# OpenRing_MCU.net
KiCad netlist of a schematic drawn in Altium Designer
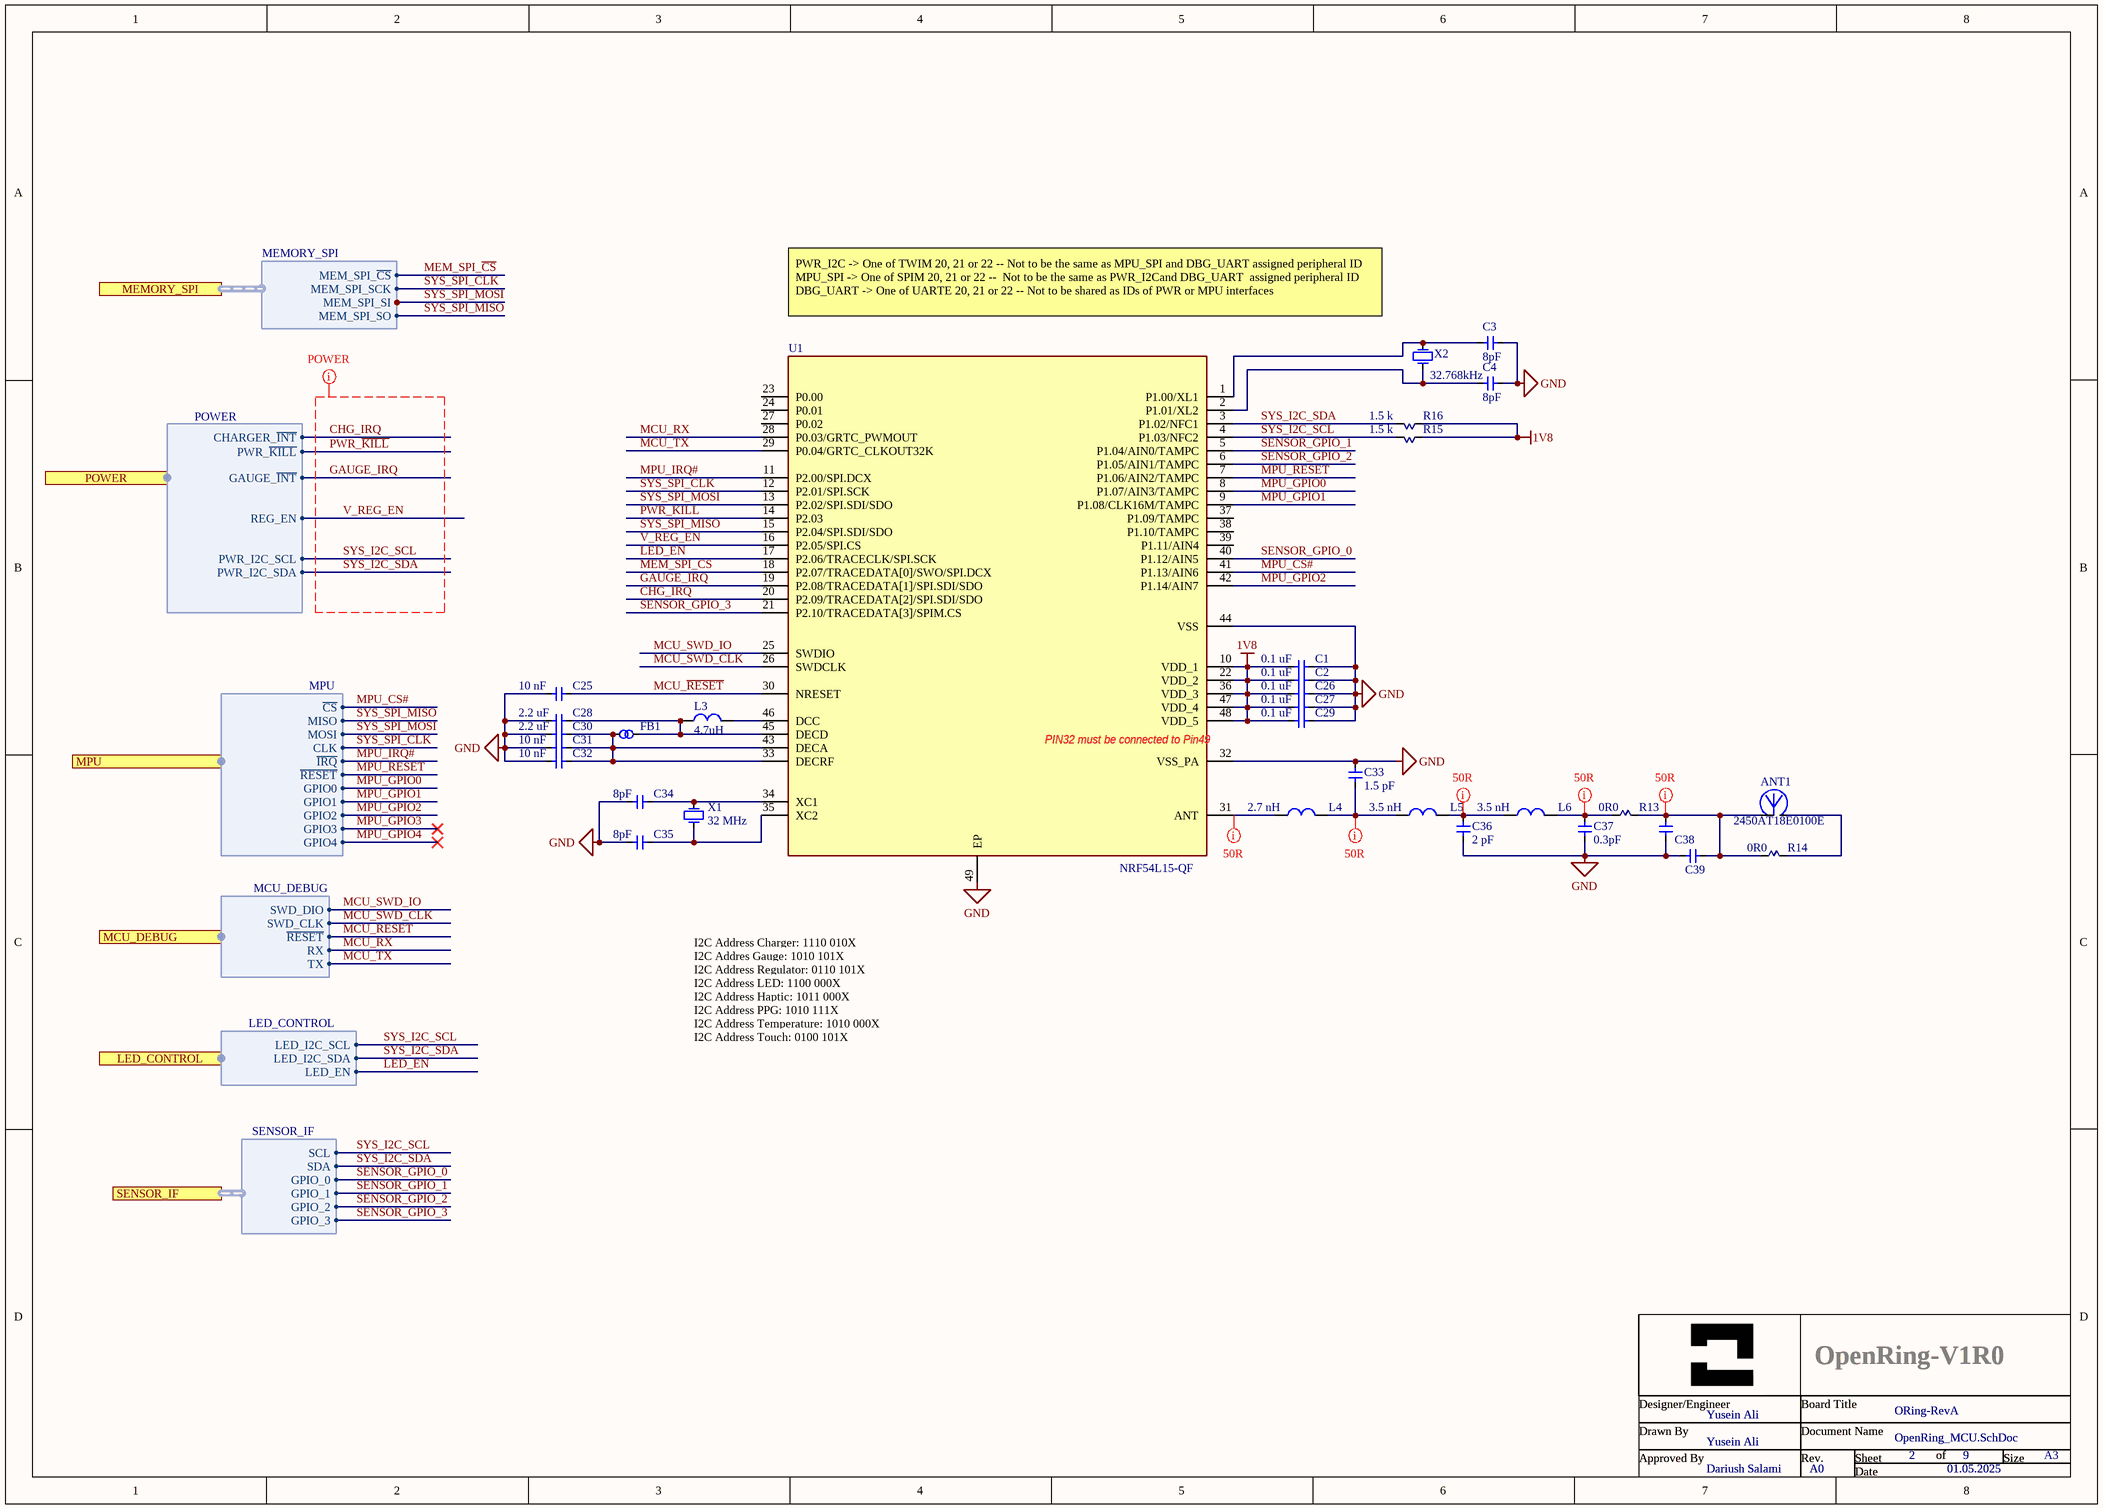
[diagram p0: OpenRing_MCU.SchDoc]

(export (version "E")
  (design (tool "Eeschema 10.0.6"))
  (components
    (comp (ref "ANT1")
      (value "2450AT18E0100E")
      (footprint "ANTC3216X130N")
      (description "7 Inch Reel / Mini 2.45Ghz Chip Antenna")
      (fields (field (name "MANUFACTURER") "Johanson") (field (name "CHECKED") "TRUE"))
      (libsource (lib "RFComponents") (part "2450AT18E0100E"))
    )
    (comp (ref "C1")
      (value "0.1 uF")
      (footprint "CAPC1005X05N")
      (description "CAP CER 0.1UF 16V X5R 0402")
      (fields
        (field (name "MANUFACTURER") "Murata Electronics")
        (field (name "MANUFACTURER PART NUMBER") "GRM155R61C104KA88D")
      )
      (libsource (lib "OpenRingComponents") (part "GRM155R61C104KA88D"))
    )
    (comp (ref "C2")
      (value "0.1 uF")
      (footprint "CAPC1005X05N")
      (description "CAP CER 0.1UF 16V X5R 0402")
      (fields
        (field (name "MANUFACTURER") "Murata Electronics")
        (field (name "MANUFACTURER PART NUMBER") "GRM155R61C104KA88D")
      )
      (libsource (lib "OpenRingComponents") (part "GRM155R61C104KA88D"))
    )
    (comp (ref "C3")
      (value "8pF")
      (footprint "CAPC1005X05N")
      (description "Multilayer Ceramic Capacitors MLCC - SMD/SMT 0402 8.0pF 50volts C0G +/-0.05pF")
      (fields
        (field (name "MANUFACTURER") "Murata")
        (field (name "MANUFACTURER PART NUMBER") "GRM1555C1H8R0BA01D")
      )
      (libsource (lib "OpenRingComponents") (part "GRM1555C1H8R0BA01D"))
    )
    (comp (ref "C4")
      (value "8pF")
      (footprint "CAPC1005X05N")
      (description "Multilayer Ceramic Capacitors MLCC - SMD/SMT 0402 8.0pF 50volts C0G +/-0.05pF")
      (fields
        (field (name "MANUFACTURER") "Murata")
        (field (name "MANUFACTURER PART NUMBER") "GRM1555C1H8R0BA01D")
      )
      (libsource (lib "OpenRingComponents") (part "GRM1555C1H8R0BA01D"))
    )
    (comp (ref "C25")
      (value "10 nF")
      (footprint "CAPC1005X05N")
      (description "CAP CER 10000PF 50V X7R 0402")
      (fields
        (field (name "MANUFACTURER") "Murata Electronics North America")
        (field (name "MANUFACTURER PART NUMBER") "GRM155R71H103KA88D")
      )
      (libsource (lib "OpenRingComponents") (part "GRM155R71H103KA88D"))
    )
    (comp (ref "C26")
      (value "0.1 uF")
      (footprint "CAPC1005X05N")
      (description "CAP CER 0.1UF 16V X5R 0402")
      (fields
        (field (name "MANUFACTURER") "Murata Electronics")
        (field (name "MANUFACTURER PART NUMBER") "GRM155R61C104KA88D")
      )
      (libsource (lib "OpenRingComponents") (part "GRM155R61C104KA88D"))
    )
    (comp (ref "C27")
      (value "0.1 uF")
      (footprint "CAPC1005X05N")
      (description "CAP CER 0.1UF 16V X5R 0402")
      (fields
        (field (name "MANUFACTURER") "Murata Electronics")
        (field (name "MANUFACTURER PART NUMBER") "GRM155R61C104KA88D")
      )
      (libsource (lib "OpenRingComponents") (part "GRM155R61C104KA88D"))
    )
    (comp (ref "C28")
      (value "2.2 uF")
      (footprint "CAPC1005X05N")
      (description "CAP CER 2.2UF 10V X5R 0402")
      (fields
        (field (name "MANUFACTURER") "Murata Electronics North America")
        (field (name "MANUFACTURER PART NUMBER") "GRM155R61A225KE95D")
      )
      (libsource (lib "OpenRingComponents") (part "GRM155R61A225KE95D"))
    )
    (comp (ref "C29")
      (value "0.1 uF")
      (footprint "CAPC1005X05N")
      (description "CAP CER 0.1UF 16V X5R 0402")
      (fields
        (field (name "MANUFACTURER") "Murata Electronics")
        (field (name "MANUFACTURER PART NUMBER") "GRM155R61C104KA88D")
      )
      (libsource (lib "OpenRingComponents") (part "GRM155R61C104KA88D"))
    )
    (comp (ref "C30")
      (value "2.2 uF")
      (footprint "CAPC1005X05N")
      (description "CAP CER 2.2UF 10V X5R 0402")
      (fields
        (field (name "MANUFACTURER") "Murata Electronics North America")
        (field (name "MANUFACTURER PART NUMBER") "GRM155R61A225KE95D")
      )
      (libsource (lib "OpenRingComponents") (part "GRM155R61A225KE95D"))
    )
    (comp (ref "C31")
      (value "10 nF")
      (footprint "CAPC1005X05N")
      (description "CAP CER 10000PF 50V X7R 0402")
      (fields
        (field (name "MANUFACTURER") "Murata Electronics North America")
        (field (name "MANUFACTURER PART NUMBER") "GRM155R71H103KA88D")
      )
      (libsource (lib "OpenRingComponents") (part "GRM155R71H103KA88D"))
    )
    (comp (ref "C32")
      (value "10 nF")
      (footprint "CAPC1005X05N")
      (description "CAP CER 10000PF 50V X7R 0402")
      (fields
        (field (name "MANUFACTURER") "Murata Electronics North America")
        (field (name "MANUFACTURER PART NUMBER") "GRM155R71H103KA88D")
      )
      (libsource (lib "OpenRingComponents") (part "GRM155R71H103KA88D"))
    )
    (comp (ref "C33")
      (value "1.5 pF")
      (footprint "CAPC1005X05N")
      (description "Multilayer Ceramic Capacitor, 1.5 pF, 50 V, ï¿½ 0.1pF, C0G (NP0), 0402 [1005 Metric]")
      (fields
        (field (name "MANUFACTURER") "Murata")
        (field (name "MANUFACTURER PART NUMBER") "GJM1555C1H1R5BB01D")
      )
      (libsource (lib "OpenRingComponents") (part "GJM1555C1H1R5BB01D"))
    )
    (comp (ref "C34")
      (value "8pF")
      (footprint "CAPC1005X05N")
      (description "Multilayer Ceramic Capacitors MLCC - SMD/SMT 0402 8.0pF 50volts C0G +/-0.05pF")
      (fields
        (field (name "MANUFACTURER") "Murata")
        (field (name "MANUFACTURER PART NUMBER") "GRM1555C1H8R0BA01D")
      )
      (libsource (lib "OpenRingComponents") (part "GRM1555C1H8R0BA01D"))
    )
    (comp (ref "C35")
      (value "8pF")
      (footprint "CAPC1005X05N")
      (description "Multilayer Ceramic Capacitors MLCC - SMD/SMT 0402 8.0pF 50volts C0G +/-0.05pF")
      (fields
        (field (name "MANUFACTURER") "Murata")
        (field (name "MANUFACTURER PART NUMBER") "GRM1555C1H8R0BA01D")
      )
      (libsource (lib "OpenRingComponents") (part "GRM1555C1H8R0BA01D"))
    )
    (comp (ref "C36")
      (value "2 pF")
      (footprint "CAPC1005X05N")
      (description "0402 2 pF 50V ±0.05 pF Tolerance C0G SMT Multilayer Ceramic Capacitor")
      (fields
        (field (name "MANUFACTURER") "Murata")
        (field (name "MANUFACTURER PART NUMBER") "GJM1555C1H2R0WB01D")
      )
      (libsource (lib "Passives") (part "GJM1555C1H2R0WB01D"))
    )
    (comp (ref "C37")
      (value "0.3pF")
      (footprint "INDC1005X06N")
      (description "0402 0.3 pF 50V ±0.05 pF Tolerance C0G SMT Multilayer Ceramic Capacitor")
      (fields
        (field (name "MANUFACTURER") "Murata")
        (field (name "MANUFACTURER PART NUMBER") "GJM1555C1HR30WB01D")
      )
      (libsource (lib "OpenRingComponents") (part "GJM1555C1HR30WB01D"))
    )
    (comp (ref "C38")
      (value "NC")
      (footprint "CAPC1005X05N")
      (libsource (lib "OpenRingComponents") (part "CAPACITOR"))
    )
    (comp (ref "C39")
      (value "NC")
      (footprint "CAPC1005X05N")
      (libsource (lib "OpenRingComponents") (part "CAPACITOR"))
    )
    (comp (ref "FB1")
      (value "BLM15AG121SN1D")
      (footprint "INDC1005X06N")
      (description "Ferrite Beads Multi-Layer 120Ohm 25% 100MHz 550mA 190mOhm DCR 0402 Paper T/R")
      (fields (field (name "MANUFACTURER") "Murata") (field (name "TOLERANCE") "25%"))
      (libsource (lib "OpenRingComponents") (part "BLM15AG121SN1D"))
    )
    (comp (ref "L3")
      (value "4.7uH")
      (footprint "INDC1005X06N")
      (description "Inductor Power Chip Shielded Multi-Layer 4.7uH 20% 1MHz Ferrite 0.08A 0.78Ohm DCR 0603 T/R")
      (fields
        (field (name "MANUFACTURER") "Murata")
        (field (name "MANUFACTURER PART NUMBER") "LQM18FN4R7M00D")
      )
      (libsource (lib "Passives") (part "LQM18FN4R7M00D"))
    )
    (comp (ref "L4")
      (value "2.7 nH")
      (footprint "INDC1005X06N")
      (description "Inductor Chip 2.7nH 0.1nH Tolerance 2-Pin 0402 Paper T/R")
      (fields
        (field (name "MANUFACTURER") "Murata")
        (field (name "MANUFACTURER PART NUMBER") "LQG15WH2N7B02D")
      )
      (libsource (lib "OpenRingComponents") (part "LQG15WH2N7B02D"))
    )
    (comp (ref "L5")
      (value "3.5 nH")
      (footprint "INDC1005X06N")
      (description "Inductor Chip 3.5nH 0.1nH Tolerance 2-Pin 0402 Paper T/R")
      (fields
        (field (name "MANUFACTURER") "Murata")
        (field (name "MANUFACTURER PART NUMBER") "LQG15WH3N5B02D")
      )
      (libsource (lib "OpenRingComponents") (part "LQG15WH3N5B02D"))
    )
    (comp (ref "L6")
      (value "3.5 nH")
      (footprint "INDC1005X06N")
      (description "Inductor Chip 3.5nH 0.1nH Tolerance 2-Pin 0402 Paper T/R")
      (fields
        (field (name "MANUFACTURER") "Murata")
        (field (name "MANUFACTURER PART NUMBER") "LQG15WH3N5B02D")
      )
      (libsource (lib "OpenRingComponents") (part "LQG15WH3N5B02D"))
    )
    (comp (ref "R13")
      (value "0R0")
      (footprint "RESC1005X04N")
      (description "RES SMD 0.0OHM JUMPER 1/10W 0402")
      (fields
        (field (name "MANUFACTURER") "Panasonic Electronic Components")
        (field (name "MANUFACTURER PART NUMBER") "ERJ-2GE0R00X")
      )
      (libsource (lib "OpenRingComponents") (part "ERJ-2GE0R00X"))
    )
    (comp (ref "R14")
      (value "0R0")
      (footprint "RESC1005X04N")
      (description "RES SMD 0.0OHM JUMPER 1/10W 0402")
      (fields
        (field (name "MANUFACTURER") "Panasonic Electronic Components")
        (field (name "MANUFACTURER PART NUMBER") "ERJ-2GE0R00X")
      )
      (libsource (lib "OpenRingComponents") (part "ERJ-2GE0R00X"))
    )
    (comp (ref "R15")
      (value "1.5 k")
      (footprint "RESC1005X04N")
      (description "RES SMD 1.5K OHM 1% 1/10W 0402")
      (fields
        (field (name "MANUFACTURER") "Panasonic Electronic Components")
        (field (name "MANUFACTURER PART NUMBER") "ERJ-2RKF1501X")
      )
      (libsource (lib "OpenRingComponents") (part "ERJ-2RKF1501X"))
    )
    (comp (ref "R16")
      (value "1.5 k")
      (footprint "RESC1005X04N")
      (description "RES SMD 1.5K OHM 1% 1/10W 0402")
      (fields
        (field (name "MANUFACTURER") "Panasonic Electronic Components")
        (field (name "MANUFACTURER PART NUMBER") "ERJ-2RKF1501X")
      )
      (libsource (lib "OpenRingComponents") (part "ERJ-2RKF1501X"))
    )
    (comp (ref "U1")
      (value "NRF54L15-QF")
      (footprint "QFN40P600X600X95-49N")
      (description "nRF54L15 SoC with Arm Cortex-M33 processor")
      (fields
        (field (name "MANUFACTURER") "Nordic Semiconductor")
        (field (name "MANUFACTURER PART NUMBER") "NRF54L15-QFAA-R")
      )
      (libsource (lib "OpenRingComponents") (part "NRF54L15-QFAA-R"))
    )
    (comp (ref "X1")
      (value "32 MHz")
      (footprint "FP-ABM11W-MFG")
      (description "CRYSTAL 32.0000MHZ 8PF SMD, 2x1.6mm, RoHS")
      (fields
        (field (name "MANUFACTURER") "Abracon")
        (field (name "MANUFACTURER PART NUMBER") "ABM11W-32.0000MHZ-8-B1U-T3")
        (field (name "CHECKED") "TRUE")
      )
      (libsource (lib "Passives") (part "ABM11W-32.0000MHZ-8-B1U-T3"))
    )
    (comp (ref "X2")
      (value "32.768kHz")
      (footprint "Abracon_ABS6_2012X06L")
      (description "CRYSTAL 32.768 KHZ 12.5 PF SMD")
      (fields
        (field (name "MANUFACTURER") "Abracon Corporation")
        (field (name "MANUFACTURER PART NUMBER") "ABS06-32.768KHZ-1-T")
      )
      (libsource (lib "OpenRingComponents") (part "ABS06-32.768KHZ-1-T"))
    )
  )
  (nets
    (net (code "7") (name "/CHG_IRQ") (class "Default")
      (node (ref "U1") (pin "20") (pinfunction "P2.09/TRACEDATA[2]/SPI.SDI/SDO_20") (pintype "passive"))
    )
    (net (code "8") (name "/GAUGE_IRQ") (class "Default")
      (node (ref "U1") (pin "19") (pinfunction "P2.08/TRACEDATA[1]/SPI.SDI/SDO_19") (pintype "passive"))
    )
    (net (code "9") (name "/LED_EN") (class "Default")
      (node (ref "U1") (pin "17") (pinfunction "P2.06/TRACECLK/SPI.SCK_17") (pintype "passive"))
    )
    (net (code "10") (name "/MCU_RX") (class "Default")
      (node (ref "U1") (pin "28") (pinfunction "P0.03/GRTC_PWMOUT_28") (pintype "passive"))
    )
    (net (code "11") (name "/MCU_SWD_CLK") (class "Default")
      (node (ref "U1") (pin "26") (pinfunction "SWDCLK_26") (pintype "passive"))
    )
    (net (code "12") (name "/MCU_SWD_IO") (class "Default")
      (node (ref "U1") (pin "25") (pinfunction "SWDIO_25") (pintype "passive"))
    )
    (net (code "13") (name "/MCU_TX") (class "Default")
      (node (ref "U1") (pin "29") (pinfunction "P0.04/GRTC_CLKOUT32K_29") (pintype "passive"))
    )
    (net (code "14") (name "/MCU_~{RESET}") (class "Default")
      (node (ref "C25") (pin "2") (pinfunction "2_2") (pintype "passive"))
      (node (ref "U1") (pin "30") (pinfunction "NRESET_30") (pintype "passive"))
    )
    (net (code "15") (name "/MEM_SPI_~{CS}") (class "Default")
      (node (ref "U1") (pin "18") (pinfunction "P2.07/TRACEDATA[0]/SWO/SPI.DCX_18") (pintype "passive"))
    )
    (net (code "16") (name "/MPU_CS#") (class "Default")
      (node (ref "U1") (pin "41") (pinfunction "P1.13/AIN6_41") (pintype "passive"))
    )
    (net (code "17") (name "/MPU_GPIO0") (class "Default")
      (node (ref "U1") (pin "8") (pinfunction "P1.07/AIN3/TAMPC_8") (pintype "passive"))
    )
    (net (code "18") (name "/MPU_GPIO1") (class "Default")
      (node (ref "U1") (pin "9") (pinfunction "P1.08/CLK16M/TAMPC_9") (pintype "passive"))
    )
    (net (code "19") (name "/MPU_GPIO2") (class "Default")
      (node (ref "U1") (pin "42") (pinfunction "P1.14/AIN7_42") (pintype "passive"))
    )
    (net (code "22") (name "/MPU_IRQ#") (class "Default")
      (node (ref "U1") (pin "11") (pinfunction "P2.00/SPI.DCX_11") (pintype "passive"))
    )
    (net (code "23") (name "/MPU_~{RESET}") (class "Default")
      (node (ref "U1") (pin "7") (pinfunction "P1.06/AIN2/TAMPC_7") (pintype "passive"))
    )
    (net (code "24") (name "/PWR_~{KILL}") (class "Default")
      (node (ref "U1") (pin "14") (pinfunction "P2.03_14") (pintype "passive"))
    )
    (net (code "25") (name "/SENSOR_GPIO_0") (class "Default")
      (node (ref "U1") (pin "40") (pinfunction "P1.12/AIN5_40") (pintype "passive"))
    )
    (net (code "26") (name "/SENSOR_GPIO_1") (class "Default")
      (node (ref "U1") (pin "5") (pinfunction "P1.04/AIN0/TAMPC_5") (pintype "passive"))
    )
    (net (code "27") (name "/SENSOR_GPIO_2") (class "Default")
      (node (ref "U1") (pin "6") (pinfunction "P1.05/AIN1/TAMPC_6") (pintype "passive"))
    )
    (net (code "28") (name "/SENSOR_GPIO_3") (class "Default")
      (node (ref "U1") (pin "21") (pinfunction "P2.10/TRACEDATA[3]/SPIM.CS_21") (pintype "passive"))
    )
    (net (code "29") (name "/SYS_I2C_SCL") (class "Default")
      (node (ref "R15") (pin "2") (pinfunction "2_2") (pintype "passive"))
      (node (ref "U1") (pin "4") (pinfunction "P1.03/NFC2_4") (pintype "passive"))
    )
    (net (code "30") (name "/SYS_I2C_SDA") (class "Default")
      (node (ref "R16") (pin "2") (pinfunction "2_2") (pintype "passive"))
      (node (ref "U1") (pin "3") (pinfunction "P1.02/NFC1_3") (pintype "passive"))
    )
    (net (code "31") (name "/SYS_SPI_CLK") (class "Default")
      (node (ref "U1") (pin "12") (pinfunction "P2.01/SPI.SCK_12") (pintype "passive"))
    )
    (net (code "32") (name "/SYS_SPI_MISO") (class "Default")
      (node (ref "U1") (pin "15") (pinfunction "P2.04/SPI.SDI/SDO_15") (pintype "passive"))
    )
    (net (code "33") (name "/SYS_SPI_MOSI") (class "Default")
      (node (ref "U1") (pin "13") (pinfunction "P2.02/SPI.SDI/SDO_13") (pintype "passive"))
    )
    (net (code "34") (name "/V_REG_EN") (class "Default")
      (node (ref "U1") (pin "16") (pinfunction "P2.05/SPI.CS_16") (pintype "passive"))
    )
    (net (code "41") (name "1V8") (class "Default")
      (node (ref "C1") (pin "1") (pinfunction "1_1") (pintype "passive"))
      (node (ref "C2") (pin "1") (pinfunction "1_1") (pintype "passive"))
      (node (ref "C26") (pin "1") (pinfunction "1_1") (pintype "passive"))
      (node (ref "C27") (pin "1") (pinfunction "1_1") (pintype "passive"))
      (node (ref "C29") (pin "1") (pinfunction "1_1") (pintype "passive"))
      (node (ref "R15") (pin "1") (pinfunction "1_1") (pintype "passive"))
      (node (ref "R16") (pin "1") (pinfunction "1_1") (pintype "passive"))
      (node (ref "U1") (pin "10") (pinfunction "VDD_1_10") (pintype "passive"))
      (node (ref "U1") (pin "22") (pinfunction "VDD_2_22") (pintype "passive"))
      (node (ref "U1") (pin "36") (pinfunction "VDD_3_36") (pintype "passive"))
      (node (ref "U1") (pin "47") (pinfunction "VDD_4_47") (pintype "passive"))
      (node (ref "U1") (pin "48") (pinfunction "VDD_5_48") (pintype "passive"))
    )
    (net (code "42") (name "GND") (class "Default")
      (node (ref "C1") (pin "2") (pinfunction "2_2") (pintype "passive"))
      (node (ref "C2") (pin "2") (pinfunction "2_2") (pintype "passive"))
      (node (ref "C25") (pin "1") (pinfunction "1_1") (pintype "passive"))
      (node (ref "C26") (pin "2") (pinfunction "2_2") (pintype "passive"))
      (node (ref "C27") (pin "2") (pinfunction "2_2") (pintype "passive"))
      (node (ref "C28") (pin "1") (pinfunction "1_1") (pintype "passive"))
      (node (ref "C29") (pin "2") (pinfunction "2_2") (pintype "passive"))
      (node (ref "C3") (pin "2") (pinfunction "2_2") (pintype "passive"))
      (node (ref "C30") (pin "1") (pinfunction "1_1") (pintype "passive"))
      (node (ref "C31") (pin "1") (pinfunction "1_1") (pintype "passive"))
      (node (ref "C32") (pin "1") (pinfunction "1_1") (pintype "passive"))
      (node (ref "C33") (pin "2") (pinfunction "2_2") (pintype "passive"))
      (node (ref "C34") (pin "1") (pinfunction "1_1") (pintype "passive"))
      (node (ref "C35") (pin "1") (pinfunction "1_1") (pintype "passive"))
      (node (ref "C36") (pin "1") (pinfunction "1_1") (pintype "passive"))
      (node (ref "C37") (pin "1") (pinfunction "1_1") (pintype "passive"))
      (node (ref "C38") (pin "1") (pinfunction "1_1") (pintype "passive"))
      (node (ref "C39") (pin "2") (pinfunction "2_2") (pintype "passive"))
      (node (ref "C4") (pin "1") (pinfunction "1_1") (pintype "passive"))
      (node (ref "U1") (pin "32") (pinfunction "VSS_PA_32") (pintype "passive"))
      (node (ref "U1") (pin "44") (pinfunction "VSS_44") (pintype "passive"))
      (node (ref "U1") (pin "49") (pinfunction "EP_49") (pintype "passive"))
    )
    (net (code "43") (name "Net-(ANT1-Pad1)") (class "Default")
      (node (ref "ANT1") (pin "1") (pinfunction "1_1") (pintype "passive"))
      (node (ref "C38") (pin "2") (pinfunction "2_2") (pintype "passive"))
      (node (ref "C39") (pin "1") (pinfunction "1_1") (pintype "passive"))
      (node (ref "R13") (pin "2") (pinfunction "2_2") (pintype "passive"))
      (node (ref "R14") (pin "1") (pinfunction "1_1") (pintype "passive"))
    )
    (net (code "44") (name "Net-(ANT1-Pad2)") (class "Default")
      (node (ref "ANT1") (pin "2") (pinfunction "2_2") (pintype "passive"))
      (node (ref "R14") (pin "2") (pinfunction "2_2") (pintype "passive"))
    )
    (net (code "45") (name "Net-(C33-Pad1)") (class "Default")
      (node (ref "C33") (pin "1") (pinfunction "1_1") (pintype "passive"))
      (node (ref "L4") (pin "2") (pinfunction "2_2") (pintype "passive"))
      (node (ref "L5") (pin "1") (pinfunction "1_1") (pintype "passive"))
    )
    (net (code "46") (name "Net-(C36-Pad2)") (class "Default")
      (node (ref "C36") (pin "2") (pinfunction "2_2") (pintype "passive"))
      (node (ref "L5") (pin "2") (pinfunction "2_2") (pintype "passive"))
      (node (ref "L6") (pin "1") (pinfunction "1_1") (pintype "passive"))
    )
    (net (code "47") (name "Net-(C37-Pad2)") (class "Default")
      (node (ref "C37") (pin "2") (pinfunction "2_2") (pintype "passive"))
      (node (ref "L6") (pin "2") (pinfunction "2_2") (pintype "passive"))
      (node (ref "R13") (pin "1") (pinfunction "1_1") (pintype "passive"))
    )
    (net (code "48") (name "Net-(U1-ANT)") (class "Default")
      (node (ref "L4") (pin "1") (pinfunction "1_1") (pintype "passive"))
      (node (ref "U1") (pin "31") (pinfunction "ANT_31") (pintype "passive"))
    )
    (net (code "49") (name "Net-(U1-DCC)") (class "Default")
      (node (ref "L3") (pin "2") (pinfunction "2_2") (pintype "passive"))
      (node (ref "U1") (pin "46") (pinfunction "DCC_46") (pintype "passive"))
    )
    (net (code "50") (name "Net-(U1-DECA)") (class "Default")
      (node (ref "C30") (pin "2") (pinfunction "2_2") (pintype "passive"))
      (node (ref "C31") (pin "2") (pinfunction "2_2") (pintype "passive"))
      (node (ref "C32") (pin "2") (pinfunction "2_2") (pintype "passive"))
      (node (ref "FB1") (pin "1") (pinfunction "1_1") (pintype "passive"))
      (node (ref "U1") (pin "33") (pinfunction "DECRF_33") (pintype "passive"))
      (node (ref "U1") (pin "43") (pinfunction "DECA_43") (pintype "passive"))
    )
    (net (code "51") (name "Net-(U1-DECD)") (class "Default")
      (node (ref "C28") (pin "2") (pinfunction "2_2") (pintype "passive"))
      (node (ref "FB1") (pin "2") (pinfunction "2_2") (pintype "passive"))
      (node (ref "L3") (pin "1") (pinfunction "1_1") (pintype "passive"))
      (node (ref "U1") (pin "45") (pinfunction "DECD_45") (pintype "passive"))
    )
    (net (code "52") (name "Net-(U1-P1.00{slash}XL1)") (class "Default")
      (node (ref "C3") (pin "1") (pinfunction "1_1") (pintype "passive"))
      (node (ref "U1") (pin "1") (pinfunction "P1.00/XL1_1") (pintype "passive"))
      (node (ref "X2") (pin "2") (pinfunction "OSC2_2") (pintype "passive"))
    )
    (net (code "53") (name "Net-(U1-P1.01{slash}XL2)") (class "Default")
      (node (ref "C4") (pin "2") (pinfunction "2_2") (pintype "passive"))
      (node (ref "U1") (pin "2") (pinfunction "P1.01/XL2_2") (pintype "passive"))
      (node (ref "X2") (pin "1") (pinfunction "OSC1_1") (pintype "passive"))
    )
    (net (code "54") (name "Net-(U1-XC1)") (class "Default")
      (node (ref "C34") (pin "2") (pinfunction "2_2") (pintype "passive"))
      (node (ref "U1") (pin "34") (pinfunction "XC1_34") (pintype "passive"))
      (node (ref "X1") (pin "3") (pinfunction "OSC2_3") (pintype "passive"))
    )
    (net (code "55") (name "Net-(U1-XC2)") (class "Default")
      (node (ref "C35") (pin "2") (pinfunction "2_2") (pintype "passive"))
      (node (ref "U1") (pin "35") (pinfunction "XC2_35") (pintype "passive"))
      (node (ref "X1") (pin "1") (pinfunction "OSC1_1") (pintype "passive"))
    )
    (net (code "56") (name "unconnected-(U1-P0.00-Pad23)") (class "Default")
      (node (ref "U1") (pin "23") (pinfunction "P0.00_23") (pintype "passive"))
    )
    (net (code "57") (name "unconnected-(U1-P0.01-Pad24)") (class "Default")
      (node (ref "U1") (pin "24") (pinfunction "P0.01_24") (pintype "passive"))
    )
    (net (code "58") (name "unconnected-(U1-P0.02-Pad27)") (class "Default")
      (node (ref "U1") (pin "27") (pinfunction "P0.02_27") (pintype "passive"))
    )
    (net (code "59") (name "unconnected-(U1-P1.09{slash}TAMPC-Pad37)") (class "Default")
      (node (ref "U1") (pin "37") (pinfunction "P1.09/TAMPC_37") (pintype "passive"))
    )
    (net (code "60") (name "unconnected-(U1-P1.10{slash}TAMPC-Pad38)") (class "Default")
      (node (ref "U1") (pin "38") (pinfunction "P1.10/TAMPC_38") (pintype "passive"))
    )
    (net (code "61") (name "unconnected-(U1-P1.11{slash}AIN4-Pad39)") (class "Default")
      (node (ref "U1") (pin "39") (pinfunction "P1.11/AIN4_39") (pintype "passive"))
    )
  )
)
